# Feather_Wing_Grow_Light.net
KiCad netlist of a schematic drawn in EAGLE
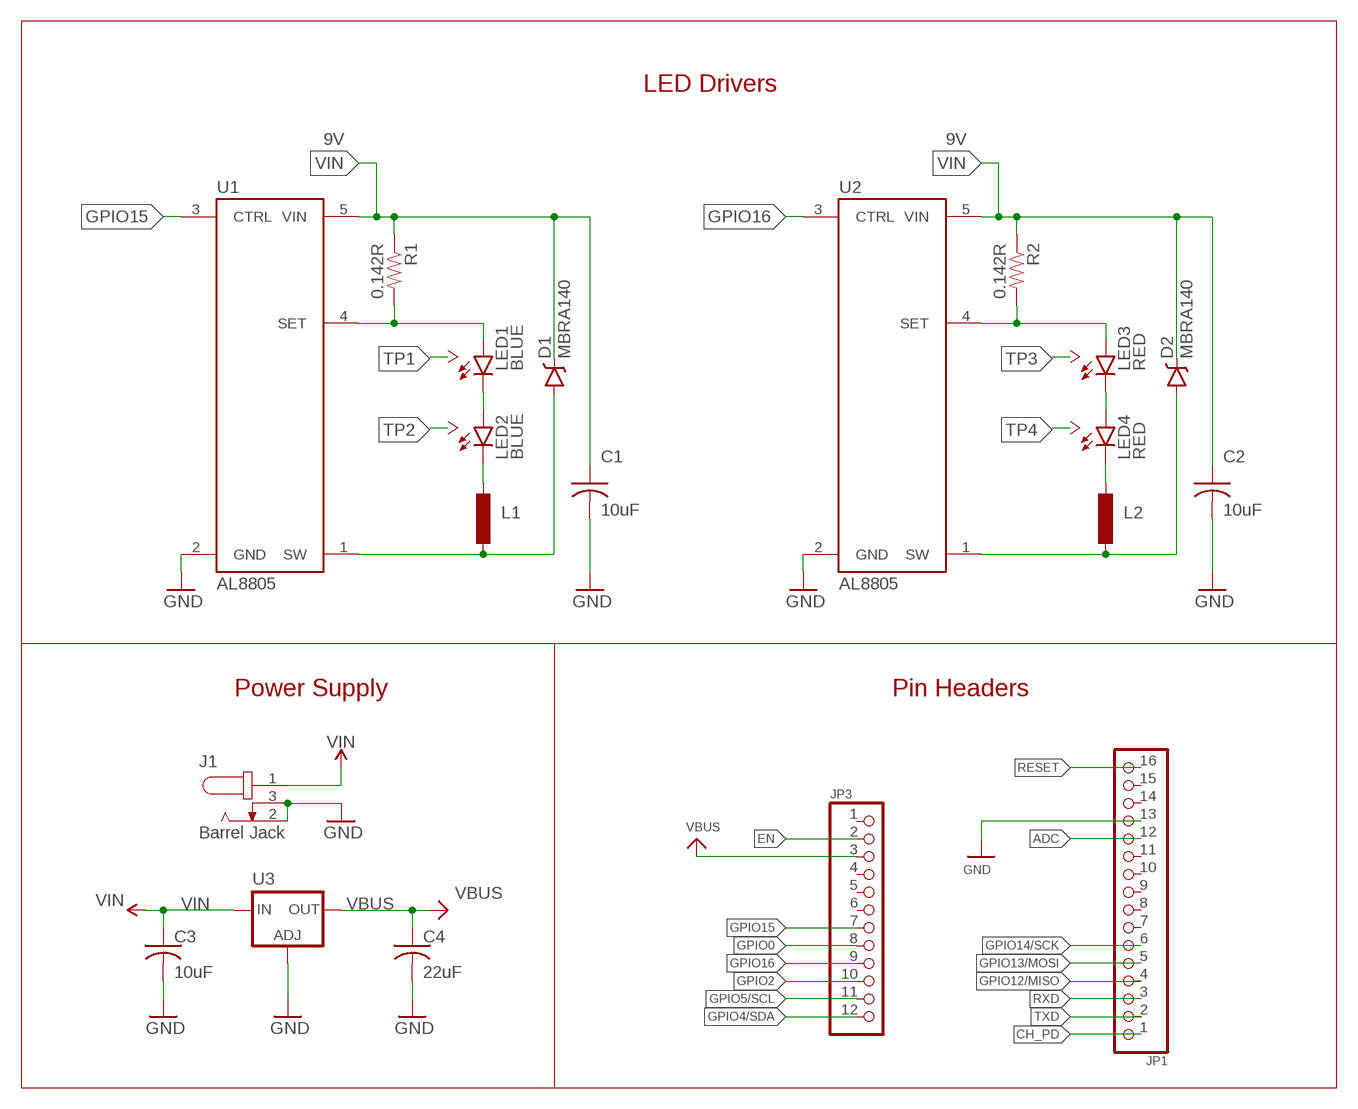
[diagram p0: schematic, sheet 1]

(export (version "E")
  (design (tool "Eeschema 10.0.6"))
  (components
    (comp (ref "C1")
      (value "10uF")
      (footprint "eagle-import:C0805")
      (libsource (lib "eagle-import") (part "C-USC0805"))
    )
    (comp (ref "C2")
      (value "10uF")
      (footprint "eagle-import:C0805")
      (libsource (lib "eagle-import") (part "C-USC0805"))
    )
    (comp (ref "C3")
      (value "10uF")
      (footprint "eagle-import:C0805")
      (libsource (lib "eagle-import") (part "C-USC0805"))
    )
    (comp (ref "C4")
      (value "22uF")
      (footprint "eagle-import:C0805")
      (libsource (lib "eagle-import") (part "C-USC0805"))
    )
    (comp (ref "D1")
      (value "MBRA140")
      (footprint "eagle-import:SMA-DIODE")
      (libsource (lib "eagle-import") (part "DIODE-SCHOTTKY-MBRA140"))
    )
    (comp (ref "D2")
      (value "MBRA140")
      (footprint "eagle-import:SMA-DIODE")
      (libsource (lib "eagle-import") (part "DIODE-SCHOTTKY-MBRA140"))
    )
    (comp (ref "J1")
      (value "Barrel Jack")
      (footprint "eagle-import:CUI_PJ-014D")
      (fields (field (name "MANUFACTURER") "CUI INC"))
      (libsource (lib "eagle-import") (part "PJ-014D"))
    )
    (comp (ref "JP1")
      (value "HEADER-1X16ROUND")
      (footprint "eagle-import:1X16_ROUND")
      (libsource (lib "eagle-import") (part "HEADER-1X16ROUND"))
    )
    (comp (ref "JP3")
      (value "HEADER-1X12")
      (footprint "eagle-import:1X12_ROUND")
      (libsource (lib "eagle-import") (part "HEADER-1X12"))
    )
    (comp (ref "L1")
      (value "33uH")
      (footprint "eagle-import:0207_10")
      (libsource (lib "eagle-import") (part "L-EU0207/10"))
    )
    (comp (ref "L2")
      (value "3.3µH/±30%/3.4A")
      (footprint "eagle-import:0207_10")
      (libsource (lib "eagle-import") (part "L-EU0207/10"))
    )
    (comp (ref "LED1")
      (value "BLUE")
      (footprint "eagle-import:CREE_XLAMP")
      (libsource (lib "eagle-import") (part "XPEWHT-01-0000-00BC2"))
    )
    (comp (ref "LED2")
      (value "BLUE")
      (footprint "eagle-import:CREE_XLAMP")
      (libsource (lib "eagle-import") (part "XPEWHT-01-0000-00BC2"))
    )
    (comp (ref "LED3")
      (value "RED")
      (footprint "eagle-import:CREE_XLAMP")
      (libsource (lib "eagle-import") (part "XPEWHT-01-0000-00BC2"))
    )
    (comp (ref "LED4")
      (value "RED")
      (footprint "eagle-import:CREE_XLAMP")
      (libsource (lib "eagle-import") (part "XPEWHT-01-0000-00BC2"))
    )
    (comp (ref "R1")
      (value "0.142R")
      (footprint "eagle-import:0805")
      (libsource (lib "eagle-import") (part "0.3OHM-1/8W-1%(0805)"))
    )
    (comp (ref "R2")
      (value "0.142R")
      (footprint "eagle-import:0805")
      (libsource (lib "eagle-import") (part "0.3OHM-1/8W-1%(0805)"))
    )
    (comp (ref "U1")
      (value "AL8805")
      (footprint "eagle-import:SOT23-5")
      (libsource (lib "eagle-import") (part "AL8805"))
    )
    (comp (ref "U2")
      (value "AL8805")
      (footprint "eagle-import:SOT23-5")
      (libsource (lib "eagle-import") (part "AL8805"))
    )
    (comp (ref "U3")
      (value "LM1117SOT223-REFLOW")
      (footprint "eagle-import:SOT223-R")
      (libsource (lib "eagle-import") (part "LM1117SOT223-REFLOW"))
    )
  )
  (nets
    (net (code "1") (name "ADC") (class "Default")
      (node (ref "JP1") (pin "12") (pinfunction "12_12") (pintype "passive"))
    )
    (net (code "2") (name "CH_PD") (class "Default")
      (node (ref "JP1") (pin "1") (pinfunction "1_1") (pintype "passive"))
    )
    (net (code "3") (name "EN") (class "Default")
      (node (ref "JP3") (pin "2") (pinfunction "2_2") (pintype "passive"))
    )
    (net (code "4") (name "GND") (class "Default")
      (node (ref "C1") (pin "2") (pinfunction "2_2") (pintype "passive"))
      (node (ref "C2") (pin "2") (pinfunction "2_2") (pintype "passive"))
      (node (ref "C3") (pin "2") (pinfunction "2_2") (pintype "passive"))
      (node (ref "C4") (pin "2") (pinfunction "2_2") (pintype "passive"))
      (node (ref "J1") (pin "2") (pinfunction "2_2") (pintype "passive"))
      (node (ref "J1") (pin "3") (pinfunction "3_3") (pintype "passive"))
      (node (ref "JP1") (pin "13") (pinfunction "13_13") (pintype "passive"))
      (node (ref "U1") (pin "2") (pinfunction "GND_2") (pintype "bidirectional"))
      (node (ref "U2") (pin "2") (pinfunction "GND_2") (pintype "bidirectional"))
      (node (ref "U3") (pin "1") (pinfunction "ADJ_1") (pintype "input"))
    )
    (net (code "5") (name "GPIO0") (class "Default")
      (node (ref "JP3") (pin "8") (pinfunction "8_8") (pintype "passive"))
    )
    (net (code "6") (name "GPIO2") (class "Default")
      (node (ref "JP3") (pin "10") (pinfunction "10_10") (pintype "passive"))
    )
    (net (code "7") (name "GPIO4{slash}SDA") (class "Default")
      (node (ref "JP3") (pin "12") (pinfunction "12_12") (pintype "passive"))
    )
    (net (code "8") (name "GPIO5{slash}SCL") (class "Default")
      (node (ref "JP3") (pin "11") (pinfunction "11_11") (pintype "passive"))
    )
    (net (code "9") (name "GPIO12{slash}MISO") (class "Default")
      (node (ref "JP1") (pin "4") (pinfunction "4_4") (pintype "passive"))
    )
    (net (code "10") (name "GPIO13{slash}MOSI") (class "Default")
      (node (ref "JP1") (pin "5") (pinfunction "5_5") (pintype "passive"))
    )
    (net (code "11") (name "GPIO14{slash}SCK") (class "Default")
      (node (ref "JP1") (pin "6") (pinfunction "6_6") (pintype "passive"))
    )
    (net (code "12") (name "GPIO15") (class "Default")
      (node (ref "JP3") (pin "7") (pinfunction "7_7") (pintype "passive"))
      (node (ref "U1") (pin "3") (pinfunction "CTRL_3") (pintype "bidirectional"))
    )
    (net (code "13") (name "GPIO16") (class "Default")
      (node (ref "JP3") (pin "9") (pinfunction "9_9") (pintype "passive"))
      (node (ref "U2") (pin "3") (pinfunction "CTRL_3") (pintype "bidirectional"))
    )
    (net (code "14") (name "Net-(L1-Pad2)") (class "Default")
      (node (ref "L1") (pin "2") (pinfunction "2_2") (pintype "passive"))
      (node (ref "LED2") (pin "C") (pinfunction "C_C") (pintype "passive"))
      (node (ref "LED2") (pin "C@1") (pinfunction "C_C@1") (pintype "passive"))
    )
    (net (code "15") (name "Net-(L2-Pad2)") (class "Default")
      (node (ref "L2") (pin "2") (pinfunction "2_2") (pintype "passive"))
      (node (ref "LED4") (pin "C") (pinfunction "C_C") (pintype "passive"))
      (node (ref "LED4") (pin "C@1") (pinfunction "C_C@1") (pintype "passive"))
    )
    (net (code "16") (name "Net-(LED1-C-PadC@1)") (class "Default")
      (node (ref "LED1") (pin "C") (pinfunction "C_C") (pintype "passive"))
      (node (ref "LED1") (pin "C@1") (pinfunction "C_C@1") (pintype "passive"))
      (node (ref "LED2") (pin "A") (pinfunction "A_A") (pintype "passive"))
      (node (ref "LED2") (pin "A@1") (pinfunction "A_A@1") (pintype "passive"))
    )
    (net (code "17") (name "Net-(LED3-C-PadC@1)") (class "Default")
      (node (ref "LED3") (pin "C") (pinfunction "C_C") (pintype "passive"))
      (node (ref "LED3") (pin "C@1") (pinfunction "C_C@1") (pintype "passive"))
      (node (ref "LED4") (pin "A") (pinfunction "A_A") (pintype "passive"))
      (node (ref "LED4") (pin "A@1") (pinfunction "A_A@1") (pintype "passive"))
    )
    (net (code "18") (name "Net-(U1-SET)") (class "Default")
      (node (ref "LED1") (pin "A") (pinfunction "A_A") (pintype "passive"))
      (node (ref "LED1") (pin "A@1") (pinfunction "A_A@1") (pintype "passive"))
      (node (ref "R1") (pin "2") (pinfunction "2_2") (pintype "passive"))
      (node (ref "U1") (pin "4") (pinfunction "SET_4") (pintype "bidirectional"))
    )
    (net (code "19") (name "Net-(U1-SW)") (class "Default")
      (node (ref "D1") (pin "A") (pinfunction "A_A") (pintype "passive"))
      (node (ref "L1") (pin "1") (pinfunction "1_1") (pintype "passive"))
      (node (ref "U1") (pin "1") (pinfunction "SW_1") (pintype "bidirectional"))
    )
    (net (code "20") (name "Net-(U2-SET)") (class "Default")
      (node (ref "LED3") (pin "A") (pinfunction "A_A") (pintype "passive"))
      (node (ref "LED3") (pin "A@1") (pinfunction "A_A@1") (pintype "passive"))
      (node (ref "R2") (pin "2") (pinfunction "2_2") (pintype "passive"))
      (node (ref "U2") (pin "4") (pinfunction "SET_4") (pintype "bidirectional"))
    )
    (net (code "21") (name "Net-(U2-SW)") (class "Default")
      (node (ref "D2") (pin "A") (pinfunction "A_A") (pintype "passive"))
      (node (ref "L2") (pin "1") (pinfunction "1_1") (pintype "passive"))
      (node (ref "U2") (pin "1") (pinfunction "SW_1") (pintype "bidirectional"))
    )
    (net (code "22") (name "RESET") (class "Default")
      (node (ref "JP1") (pin "16") (pinfunction "16_16") (pintype "passive"))
    )
    (net (code "23") (name "RXD") (class "Default")
      (node (ref "JP1") (pin "3") (pinfunction "3_3") (pintype "passive"))
    )
    (net (code "24") (name "TP1") (class "Default")
      (node (ref "LED1") (pin "X") (pinfunction "P$2_X") (pintype "bidirectional"))
    )
    (net (code "25") (name "TP2") (class "Default")
      (node (ref "LED2") (pin "X") (pinfunction "P$2_X") (pintype "bidirectional"))
    )
    (net (code "26") (name "TP3") (class "Default")
      (node (ref "LED3") (pin "X") (pinfunction "P$2_X") (pintype "bidirectional"))
    )
    (net (code "27") (name "TP4") (class "Default")
      (node (ref "LED4") (pin "X") (pinfunction "P$2_X") (pintype "bidirectional"))
    )
    (net (code "28") (name "TXD") (class "Default")
      (node (ref "JP1") (pin "2") (pinfunction "2_2") (pintype "passive"))
    )
    (net (code "29") (name "VBUS") (class "Default")
      (node (ref "C4") (pin "1") (pinfunction "1_1") (pintype "passive"))
      (node (ref "JP3") (pin "3") (pinfunction "3_3") (pintype "passive"))
      (node (ref "U3") (pin "2") (pinfunction "OUT_2") (pintype "passive"))
    )
    (net (code "30") (name "VIN") (class "Default")
      (node (ref "C1") (pin "1") (pinfunction "1_1") (pintype "passive"))
      (node (ref "C2") (pin "1") (pinfunction "1_1") (pintype "passive"))
      (node (ref "C3") (pin "1") (pinfunction "1_1") (pintype "passive"))
      (node (ref "D1") (pin "C") (pinfunction "C_C") (pintype "passive"))
      (node (ref "D2") (pin "C") (pinfunction "C_C") (pintype "passive"))
      (node (ref "J1") (pin "1") (pinfunction "1_1") (pintype "passive"))
      (node (ref "R1") (pin "1") (pinfunction "1_1") (pintype "passive"))
      (node (ref "R2") (pin "1") (pinfunction "1_1") (pintype "passive"))
      (node (ref "U1") (pin "5") (pinfunction "VIN_5") (pintype "bidirectional"))
      (node (ref "U2") (pin "5") (pinfunction "VIN_5") (pintype "bidirectional"))
      (node (ref "U3") (pin "3") (pinfunction "IN_3") (pintype "input"))
    )
    (net (code "31") (name "unconnected-(JP1-Pad7)") (class "Default")
      (node (ref "JP1") (pin "7") (pinfunction "7_7") (pintype "passive"))
    )
    (net (code "32") (name "unconnected-(JP1-Pad8)") (class "Default")
      (node (ref "JP1") (pin "8") (pinfunction "8_8") (pintype "passive"))
    )
    (net (code "33") (name "unconnected-(JP1-Pad9)") (class "Default")
      (node (ref "JP1") (pin "9") (pinfunction "9_9") (pintype "passive"))
    )
    (net (code "34") (name "unconnected-(JP1-Pad10)") (class "Default")
      (node (ref "JP1") (pin "10") (pinfunction "10_10") (pintype "passive"))
    )
    (net (code "35") (name "unconnected-(JP1-Pad11)") (class "Default")
      (node (ref "JP1") (pin "11") (pinfunction "11_11") (pintype "passive"))
    )
    (net (code "36") (name "unconnected-(JP1-Pad14)") (class "Default")
      (node (ref "JP1") (pin "14") (pinfunction "14_14") (pintype "passive"))
    )
    (net (code "37") (name "unconnected-(JP1-Pad15)") (class "Default")
      (node (ref "JP1") (pin "15") (pinfunction "15_15") (pintype "passive"))
    )
    (net (code "38") (name "unconnected-(JP3-Pad1)") (class "Default")
      (node (ref "JP3") (pin "1") (pinfunction "1_1") (pintype "passive"))
    )
    (net (code "39") (name "unconnected-(JP3-Pad4)") (class "Default")
      (node (ref "JP3") (pin "4") (pinfunction "4_4") (pintype "passive"))
    )
    (net (code "40") (name "unconnected-(JP3-Pad5)") (class "Default")
      (node (ref "JP3") (pin "5") (pinfunction "5_5") (pintype "passive"))
    )
    (net (code "41") (name "unconnected-(JP3-Pad6)") (class "Default")
      (node (ref "JP3") (pin "6") (pinfunction "6_6") (pintype "passive"))
    )
  )
)
